# Power_Board_5V.net
KiCad netlist of a schematic drawn in Altium Designer
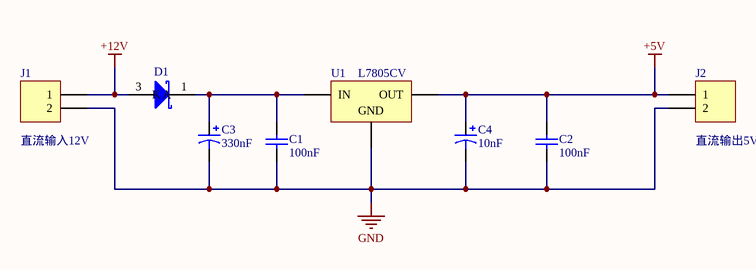
[diagram p0: Power_Board_5V.SchDoc]

(export (version "E")
  (design (tool "Eeschema 10.0.6"))
  (components
    (comp (ref "C1")
      (value "100nF")
      (footprint "cap ceramic down")
      (description "Capacitor")
      (fields (field (name "Comment") "Cap") (field (name "PUBLISHER") "Altium Limited"))
      (libsource (lib "Miscellaneous Devices") (part "Cap"))
    )
    (comp (ref "C2")
      (value "100nF")
      (footprint "cap ceramic down")
      (description "Capacitor")
      (fields (field (name "Comment") "Cap") (field (name "PUBLISHER") "Altium Limited"))
      (libsource (lib "Miscellaneous Devices") (part "Cap"))
    )
    (comp (ref "C3")
      (value "330nF")
      (footprint "cap pol")
      (description "Polarized Capacitor (Radial)")
      (fields (field (name "Comment") "Cap Pol1") (field (name "PUBLISHER") "Altium Limited"))
      (libsource (lib "Miscellaneous Devices") (part "Cap Pol1"))
    )
    (comp (ref "C4")
      (value "10nF")
      (footprint "cap pol")
      (description "Polarized Capacitor (Radial)")
      (fields (field (name "Comment") "Cap Pol1") (field (name "PUBLISHER") "Altium Limited"))
      (libsource (lib "Miscellaneous Devices") (part "Cap Pol1"))
    )
    (comp (ref "D1")
      (value "Diode 10TQ035")
      (footprint "DO-35")
      (description "Schottky Rectifier")
      (fields (field (name "PUBLISHER") "Altium Limited"))
      (libsource (lib "Miscellaneous Devices") (part "Diode 10TQ035"))
    )
    (comp (ref "J1")
      (value "Header 2")
      (footprint "Con-2")
      (description "Header, 2-Pin")
      (fields (field (name "PUBLISHER") "Altium Limited"))
      (libsource (lib "Miscellaneous Connectors") (part "Header 2"))
    )
    (comp (ref "J2")
      (value "Header 2")
      (footprint "Con-2")
      (description "Header, 2-Pin")
      (fields (field (name "PUBLISHER") "Altium Limited"))
      (libsource (lib "") (part "Header 2_1"))
    )
    (comp (ref "U1")
      (value "L7805CV")
      (footprint "TO220")
      (description "Positive Voltage Regulator, 5V, 3-Pin TO-220")
      (libsource (lib "Altium Content Vault") (part "PM-REG-L4940-SIL3"))
    )
  )
  (nets
    (net (code "1") (name "+5V") (class "Default")
      (node (ref "C2") (pin "2") (pinfunction "2_2") (pintype "passive"))
      (node (ref "C4") (pin "1") (pinfunction "1_1") (pintype "passive"))
      (node (ref "J2") (pin "1") (pinfunction "1_1") (pintype "passive"))
      (node (ref "U1") (pin "3") (pinfunction "OUT_3") (pintype "power_in"))
    )
    (net (code "2") (name "+12V") (class "Default")
      (node (ref "D1") (pin "3") (pinfunction "A_3") (pintype "passive"))
      (node (ref "J1") (pin "1") (pinfunction "1_1") (pintype "passive"))
    )
    (net (code "3") (name "GND") (class "Default")
      (node (ref "C1") (pin "2") (pinfunction "2_2") (pintype "passive"))
      (node (ref "C2") (pin "1") (pinfunction "1_1") (pintype "passive"))
      (node (ref "C3") (pin "2") (pinfunction "2_2") (pintype "passive"))
      (node (ref "C4") (pin "2") (pinfunction "2_2") (pintype "passive"))
      (node (ref "J1") (pin "2") (pinfunction "2_2") (pintype "passive"))
      (node (ref "J2") (pin "2") (pinfunction "2_2") (pintype "passive"))
      (node (ref "U1") (pin "2") (pinfunction "GND_2") (pintype "power_in"))
    )
    (net (code "4") (name "Net-(D1-K)") (class "Default")
      (node (ref "C1") (pin "1") (pinfunction "1_1") (pintype "passive"))
      (node (ref "C3") (pin "1") (pinfunction "1_1") (pintype "passive"))
      (node (ref "D1") (pin "1") (pinfunction "K_1") (pintype "passive"))
      (node (ref "U1") (pin "1") (pinfunction "IN_1") (pintype "power_in"))
    )
  )
)
